# G.net
KiCad netlist of a schematic drawn in Altium Designer
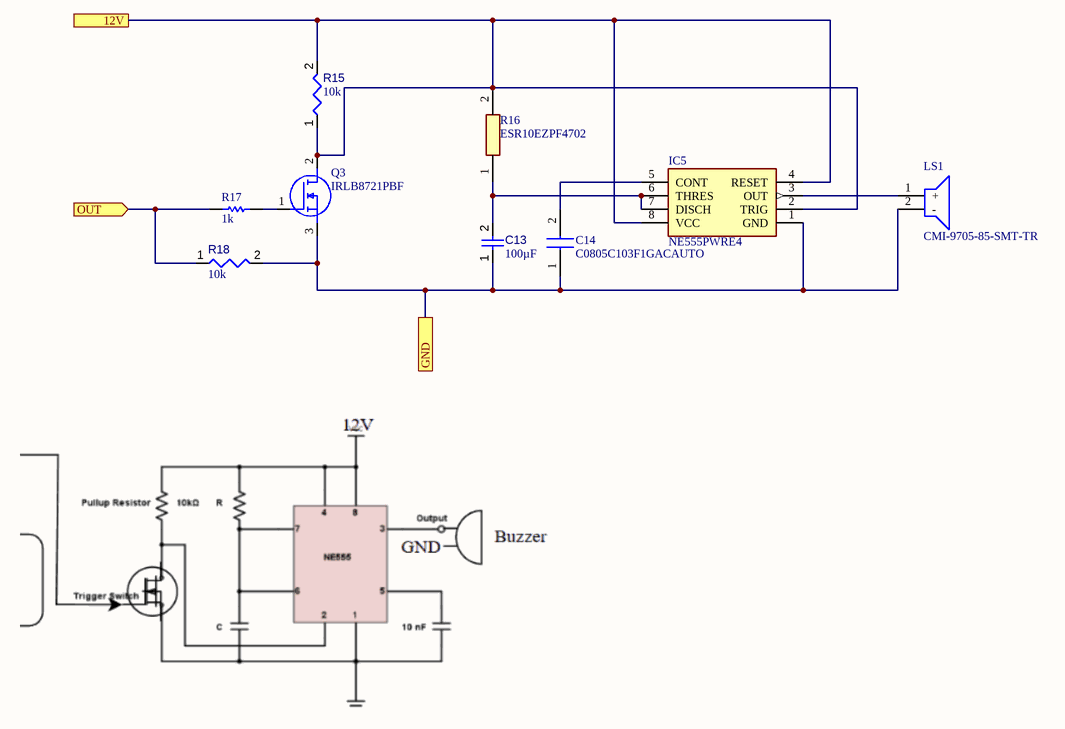
[diagram p0: G.SchDoc]

(export (version "E")
  (design (tool "Eeschema 10.0.6"))
  (components
    (comp (ref "C13")
      (value "100µF")
      (footprint "CAPC0805(2012)145_L")
      (description "Chip Capacitor, 100µF +/-20%, 6.3V, 0805, Thickness 1.45 mm")
      (fields (field (name "TOLERANCE") "10%") (field (name "Comment") "Capacitor 100µF +/-20% 6.3V 0805"))
      (libsource (lib "Hector Dela Rosa") (part "CAP-NP-2"))
    )
    (comp (ref "C14")
      (value "C0805C103F1GACAUTO")
      (footprint "SamacSys:C0805")
      (description "Capacitor")
      (fields (field (name "MOUSER PART NUMBER") "80-C0805C103F1GAUTO"))
      (libsource (lib "*") (part "C0805C103F1GACAUTO"))
    )
    (comp (ref "IC5")
      (value "NE555PWRE4")
      (footprint "SamacSys:SOP65P640X120-8N")
      (description "Integrated Circuit")
      (fields (field (name "MOUSER PART NUMBER") "595-NE555PWRE4"))
      (libsource (lib "*") (part "NE555PWRE4"))
    )
    (comp (ref "LS1")
      (value "CMI-9705-85-SMT-TR")
      (footprint "SamacSys:CMI970585SMTTR")
      (description "Loudspeaker or Buzzer")
      (fields (field (name "MOUSER PART NUMBER") "490-CMI-9705-85SMTTR"))
      (libsource (lib "*") (part "CMI-9705-85-SMT-TR"))
    )
    (comp (ref "Q3")
      (value "IRLB8721PBF")
      (footprint "SamacSys:TO254P483X1016X1994-3P")
      (description "MOSFET (N-Channel)")
      (fields (field (name "MOUSER PART NUMBER") "942-IRLB8721PBF"))
      (libsource (lib "*") (part "IRLB8721PBF"))
    )
    (comp (ref "R15")
      (value "10k")
      (footprint "RESC2013X50X35ML15T15")
      (description "Chip Resistor, 10 KOhm, +/- 1%, 125 mW, -55 to 155 degC, 0805 (2012 Metric)")
      (fields (field (name "TOLERANCE") "1%") (field (name "POWER") "125mW"))
      (libsource (lib "") (part "RES-2_1"))
    )
    (comp (ref "R16")
      (value "ESR10EZPF4702")
      (footprint "SamacSys:RESC2012X65N")
      (description "Resistor")
      (fields (field (name "MOUSER PART NUMBER") "755-ESR10EZPF4702"))
      (libsource (lib "*") (part "ESR10EZPF4702"))
    )
    (comp (ref "R17")
      (value "1k")
      (footprint "RESC3116X70X50ML13T20")
      (description "Chip Resistor, 1 KOhm, +/- 1%, 0.25 W, -55 to 155 degC, 1206 (3216 Metric)")
      (fields (field (name "TOLERANCE") "1%") (field (name "POWER") "250mW"))
      (libsource (lib "Hector Dela Rosa") (part "RES-2"))
    )
    (comp (ref "R18")
      (value "10k")
      (footprint "RESC2013X50X35ML15T15")
      (description "Chip Resistor, 10 KOhm, +/- 1%, 125 mW, -55 to 155 degC, 0805 (2012 Metric)")
      (fields (field (name "TOLERANCE") "1%") (field (name "POWER") "125mW"))
      (libsource (lib "") (part "RES-2_1"))
    )
  )
  (nets
    (net (code "1") (name "/12V") (class "Default")
      (node (ref "IC5") (pin "2") (pinfunction "TRIG_2") (pintype "passive"))
      (node (ref "IC5") (pin "4") (pinfunction "RESET_4") (pintype "passive"))
      (node (ref "IC5") (pin "8") (pinfunction "VCC_8") (pintype "power_in"))
      (node (ref "Q3") (pin "2") (pinfunction "D_2") (pintype "passive"))
      (node (ref "R15") (pin "1") (pinfunction "1_1") (pintype "passive"))
      (node (ref "R15") (pin "2") (pinfunction "2_2") (pintype "passive"))
      (node (ref "R16") (pin "2") (pinfunction "2_2") (pintype "passive"))
    )
    (net (code "2") (name "/GND") (class "Default")
      (node (ref "C13") (pin "1") (pinfunction "1_1") (pintype "passive"))
      (node (ref "C14") (pin "1") (pinfunction "1_1") (pintype "passive"))
      (node (ref "IC5") (pin "1") (pinfunction "GND_1") (pintype "power_in"))
      (node (ref "LS1") (pin "2") (pinfunction "-_2") (pintype "passive"))
      (node (ref "Q3") (pin "3") (pinfunction "S_3") (pintype "passive"))
      (node (ref "R18") (pin "2") (pinfunction "2_2") (pintype "passive"))
    )
    (net (code "3") (name "/OUT") (class "Default")
      (node (ref "R17") (pin "1") (pinfunction "1_1") (pintype "passive"))
      (node (ref "R18") (pin "1") (pinfunction "1_1") (pintype "passive"))
    )
    (net (code "4") (name "Net-(IC5-CONT)") (class "Default")
      (node (ref "C14") (pin "2") (pinfunction "2_2") (pintype "passive"))
      (node (ref "IC5") (pin "5") (pinfunction "CONT_5") (pintype "passive"))
    )
    (net (code "5") (name "Net-(IC5-DISCH)") (class "Default")
      (node (ref "C13") (pin "2") (pinfunction "2_2") (pintype "passive"))
      (node (ref "IC5") (pin "6") (pinfunction "THRES_6") (pintype "passive"))
      (node (ref "IC5") (pin "7") (pinfunction "DISCH_7") (pintype "passive"))
      (node (ref "R16") (pin "1") (pinfunction "1_1") (pintype "passive"))
    )
    (net (code "6") (name "Net-(IC5-OUT)") (class "Default")
      (node (ref "IC5") (pin "3") (pinfunction "OUT_3") (pintype "output"))
      (node (ref "LS1") (pin "1") (pinfunction "+_1") (pintype "passive"))
    )
    (net (code "7") (name "Net-(Q3-G)") (class "Default")
      (node (ref "Q3") (pin "1") (pinfunction "G_1") (pintype "passive"))
      (node (ref "R17") (pin "2") (pinfunction "2_2") (pintype "passive"))
    )
  )
)
